# P4-1-17.net
KiCad netlist of a schematic drawn in EAGLE
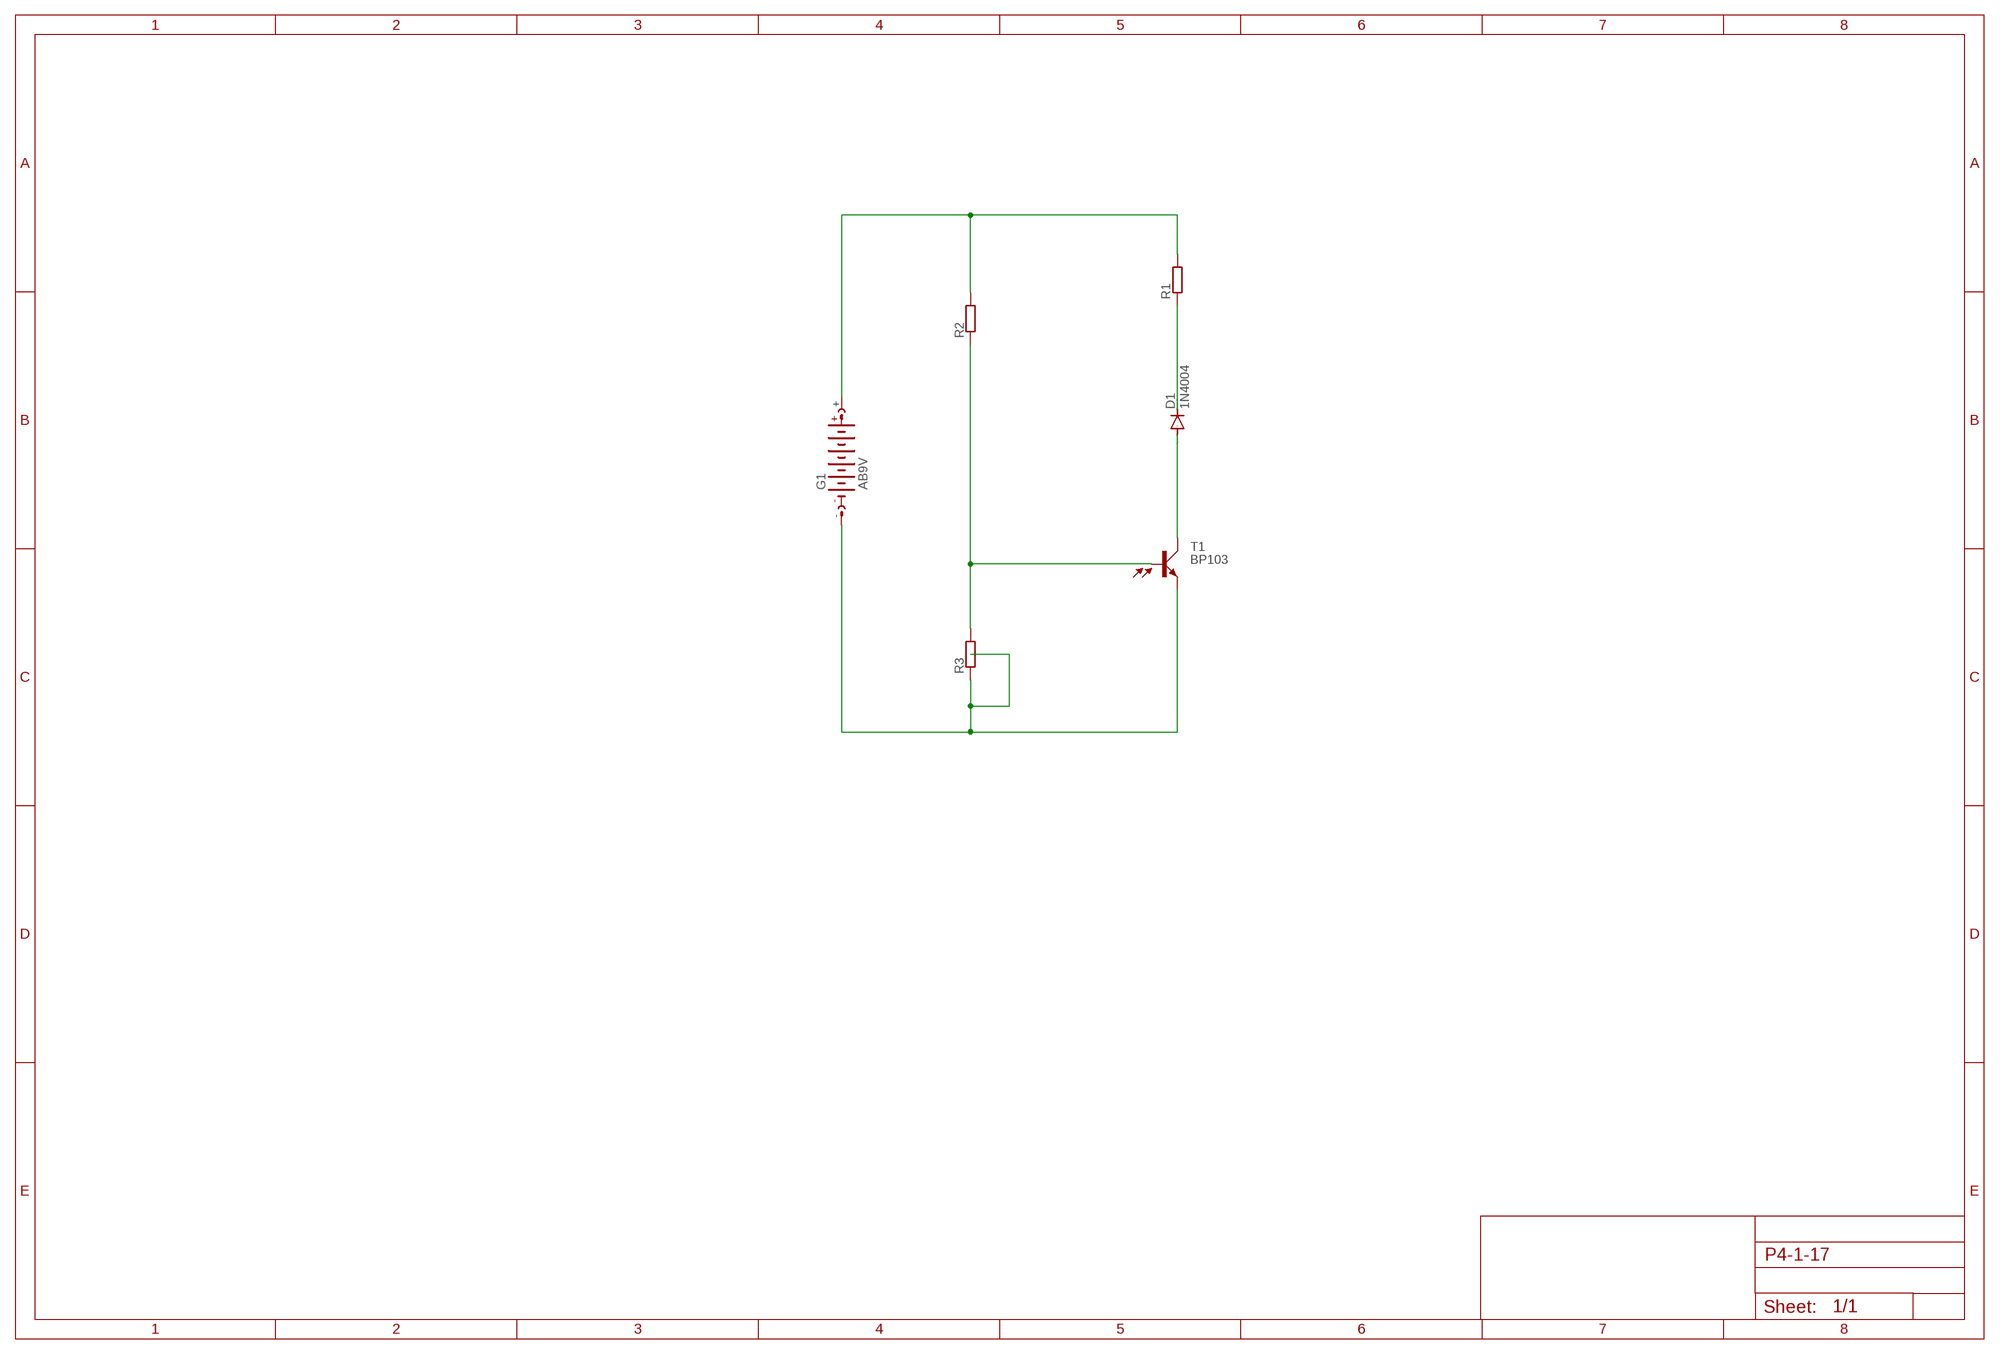
[diagram p0: schematic, sheet 1]

(export (version "E")
  (design (tool "Eeschema 10.0.6"))
  (components
    (comp (ref "D1")
      (value "1N4004")
      (footprint "eagle-import:DO41-10")
      (libsource (lib "eagle-import") (part "1N4004"))
    )
    (comp (ref "G1")
      (value "AB9V")
      (footprint "eagle-import:AB9V")
      (libsource (lib "eagle-import") (part "AB9V"))
    )
    (comp (ref "R1")
      (value "BVS")
      (footprint "eagle-import:BVS")
      (libsource (lib "eagle-import") (part "BVS"))
    )
    (comp (ref "R2")
      (value "BVS")
      (footprint "eagle-import:BVS")
      (libsource (lib "eagle-import") (part "BVS"))
    )
    (comp (ref "R3")
      (value "BVS")
      (footprint "eagle-import:BVS")
      (libsource (lib "eagle-import") (part "BVS"))
    )
    (comp (ref "T1")
      (value "BP103")
      (footprint "eagle-import:BP103")
      (libsource (lib "eagle-import") (part "BP103"))
    )
  )
  (nets
    (net (code "1") (name "Net-(D1-PadA)") (class "Default")
      (node (ref "D1") (pin "A") (pinfunction "A_A") (pintype "passive"))
      (node (ref "T1") (pin "C") (pinfunction "C_C") (pintype "passive"))
    )
    (net (code "2") (name "Net-(D1-PadC)") (class "Default")
      (node (ref "D1") (pin "C") (pinfunction "C_C") (pintype "passive"))
      (node (ref "R1") (pin "2") (pinfunction "2_2") (pintype "passive"))
    )
    (net (code "3") (name "Net-(G1-Pad+)") (class "Default")
      (node (ref "G1") (pin "+") (pinfunction "+_+") (pintype "passive"))
      (node (ref "R1") (pin "1") (pinfunction "1_1") (pintype "passive"))
      (node (ref "R2") (pin "1") (pinfunction "1_1") (pintype "passive"))
    )
    (net (code "4") (name "Net-(G1-Pad-)") (class "Default")
      (node (ref "G1") (pin "-") (pinfunction "-_-") (pintype "passive"))
      (node (ref "R3") (pin "2") (pinfunction "2_2") (pintype "passive"))
      (node (ref "T1") (pin "E") (pinfunction "E_E") (pintype "passive"))
    )
    (net (code "5") (name "Net-(R2-Pad2)") (class "Default")
      (node (ref "R2") (pin "2") (pinfunction "2_2") (pintype "passive"))
      (node (ref "R3") (pin "1") (pinfunction "1_1") (pintype "passive"))
      (node (ref "T1") (pin "B") (pinfunction "B_B") (pintype "passive"))
    )
  )
)
